# tactilePop.net
KiCad netlist of a schematic drawn in EAGLE
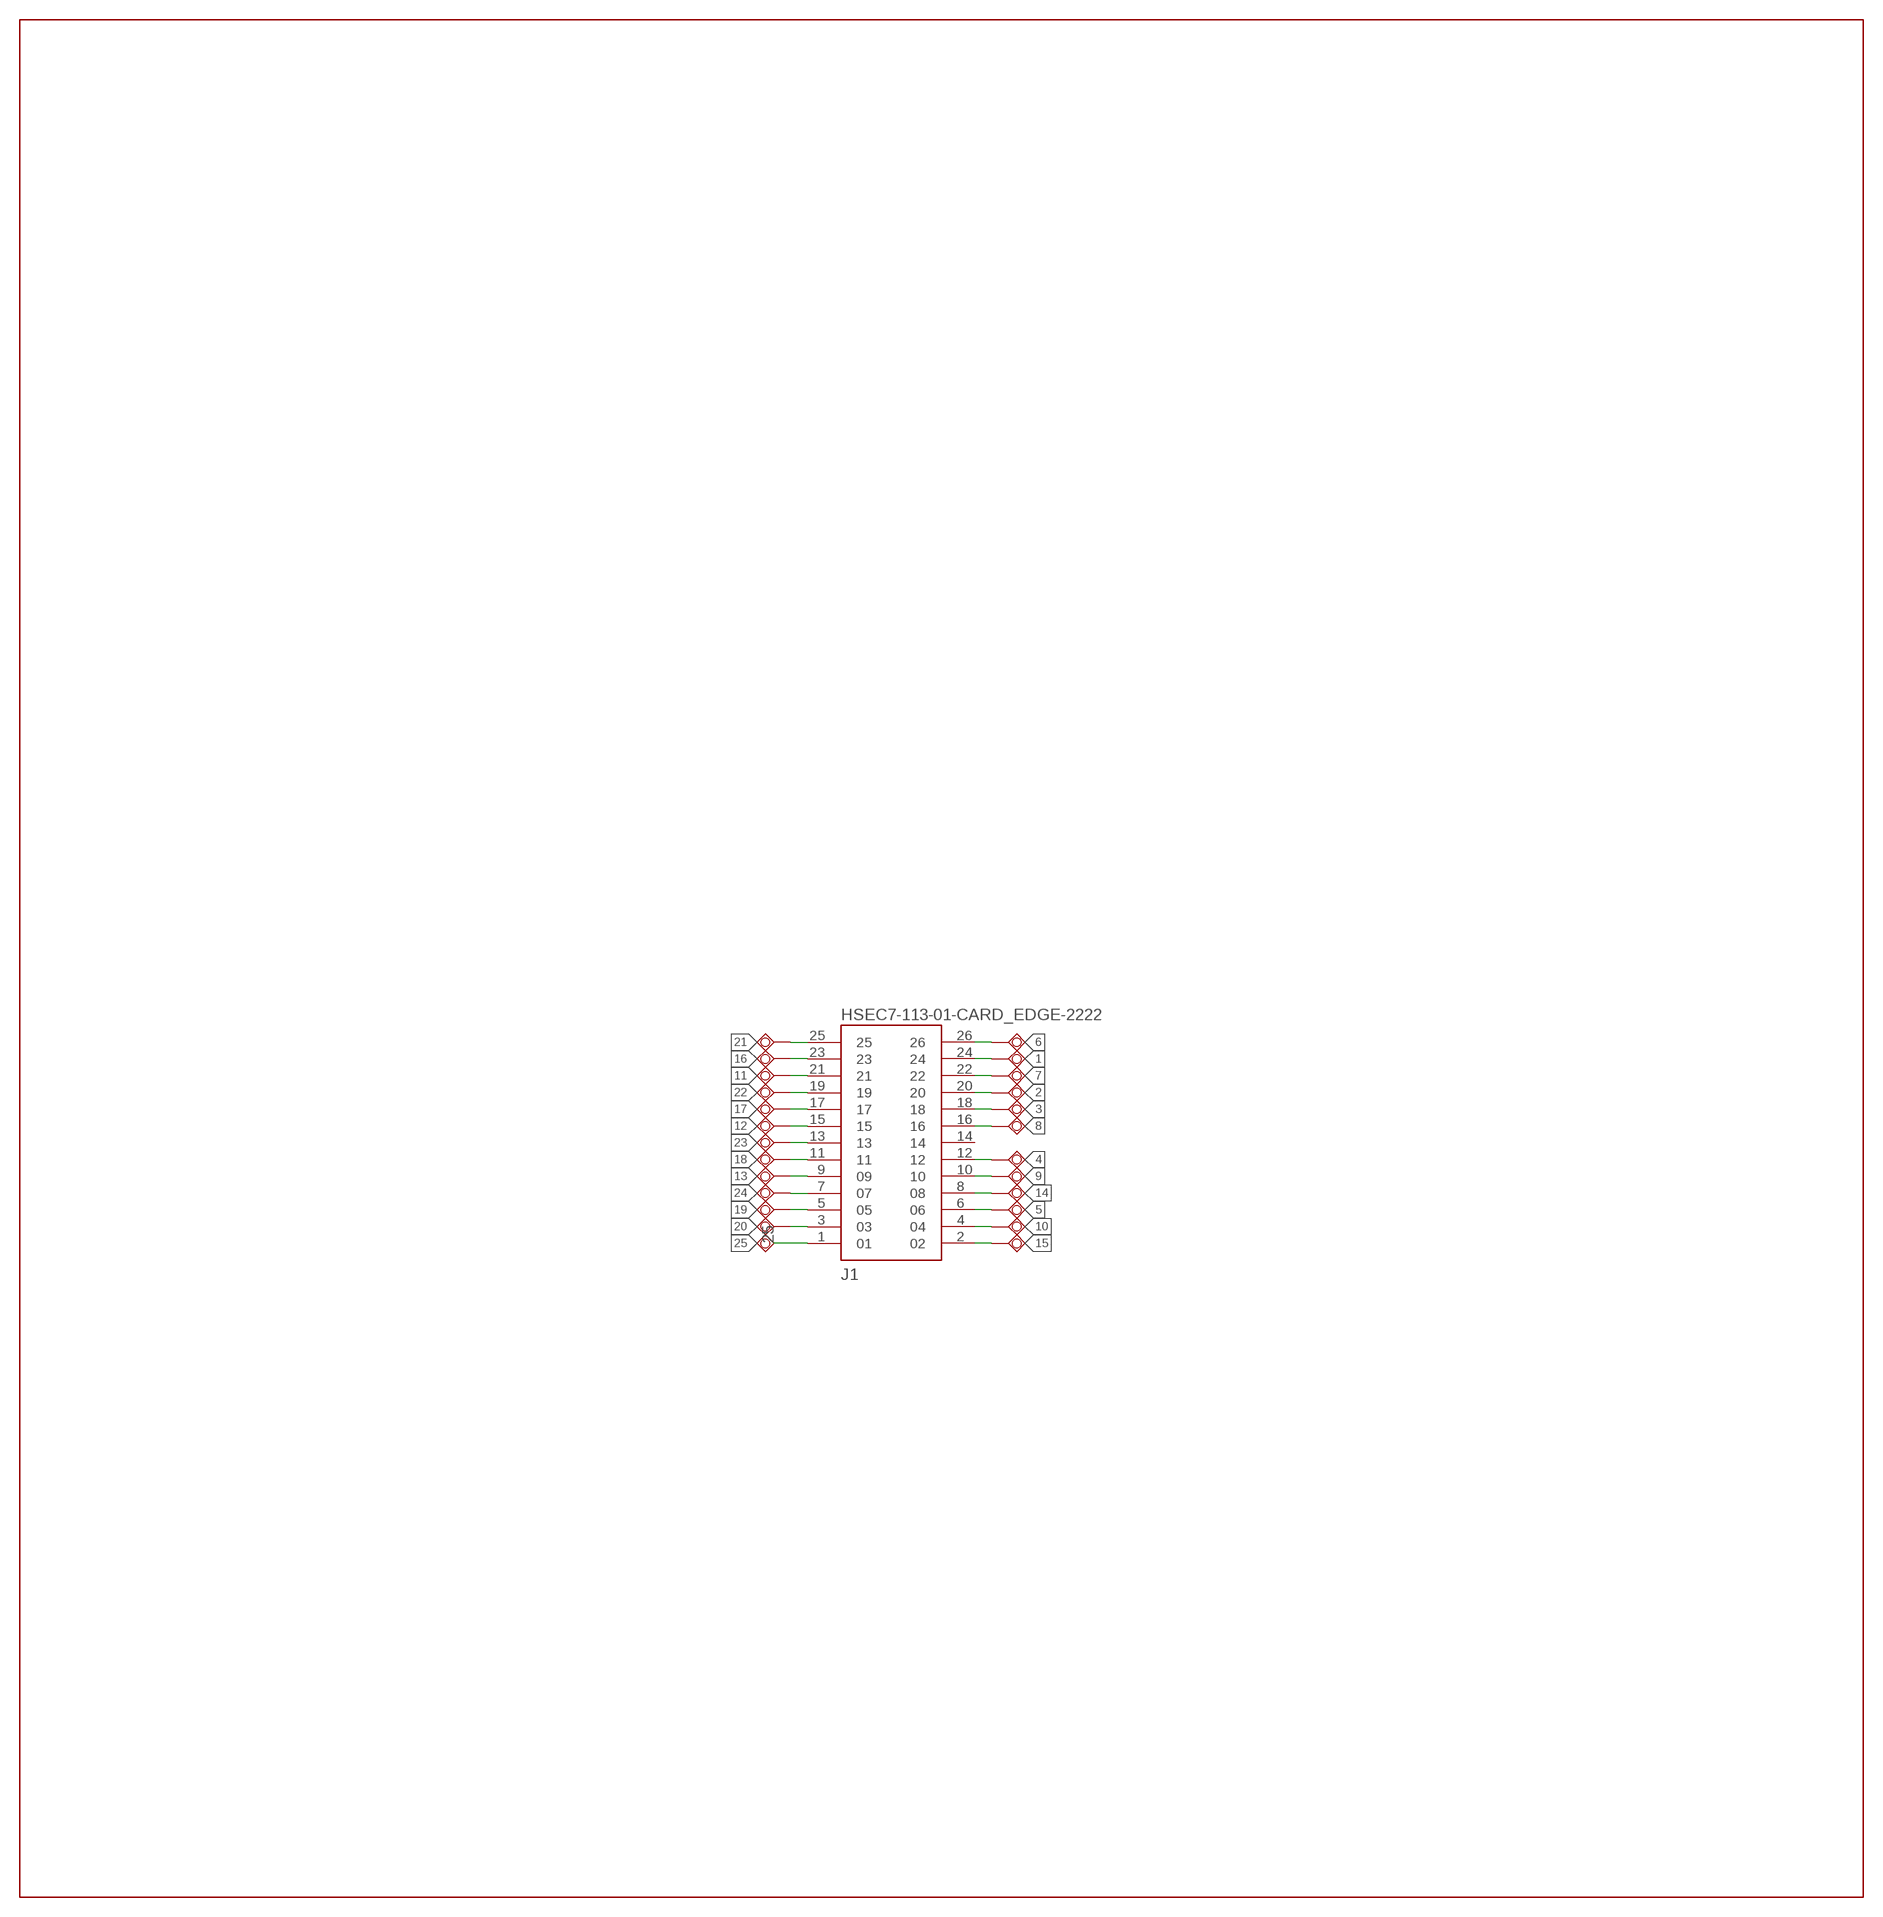
[diagram p0: schematic, sheet 1]

(export (version "E")
  (design (tool "Eeschema 10.0.6"))
  (components
    (comp (ref "1")
      (value "TESTPAD_TPSQB2,54")
      (footprint "eagle-import:TESTPAD_B2,54")
      (libsource (lib "eagle-import") (part "TESTPAD_TPSQB2,54"))
    )
    (comp (ref "2")
      (value "TESTPAD_TPSQB2,54")
      (footprint "eagle-import:TESTPAD_B2,54")
      (libsource (lib "eagle-import") (part "TESTPAD_TPSQB2,54"))
    )
    (comp (ref "3")
      (value "TESTPAD_TPSQB2,54")
      (footprint "eagle-import:TESTPAD_B2,54")
      (libsource (lib "eagle-import") (part "TESTPAD_TPSQB2,54"))
    )
    (comp (ref "J1")
      (value "HSEC7-113-01-CARD_EDGE-2222")
      (footprint "eagle-import:HSEC8-113-01-X-RA-L2")
      (libsource (lib "eagle-import") (part "HSEC7-113-01-CARD_EDGE-2222"))
    )
    (comp (ref "TP1")
      (value "TESTPAD_TPSQB2,54")
      (footprint "eagle-import:TESTPAD_B2,54")
      (libsource (lib "eagle-import") (part "TESTPAD_TPSQB2,54"))
    )
    (comp (ref "TP3")
      (value "TESTPAD_TPSQB2,54")
      (footprint "eagle-import:TESTPAD_B2,54")
      (libsource (lib "eagle-import") (part "TESTPAD_TPSQB2,54"))
    )
    (comp (ref "TP6")
      (value "TESTPAD_TPSQB2,54")
      (footprint "eagle-import:TESTPAD_B2,54")
      (libsource (lib "eagle-import") (part "TESTPAD_TPSQB2,54"))
    )
    (comp (ref "TP7")
      (value "TESTPAD_TPSQB2,54")
      (footprint "eagle-import:TESTPAD_B2,54")
      (libsource (lib "eagle-import") (part "TESTPAD_TPSQB2,54"))
    )
    (comp (ref "TP8")
      (value "TESTPAD_TPSQB2,54")
      (footprint "eagle-import:TESTPAD_B2,54")
      (libsource (lib "eagle-import") (part "TESTPAD_TPSQB2,54"))
    )
    (comp (ref "TP9")
      (value "TESTPAD_TPSQB2,54")
      (footprint "eagle-import:TESTPAD_B2,54")
      (libsource (lib "eagle-import") (part "TESTPAD_TPSQB2,54"))
    )
    (comp (ref "TP10")
      (value "TESTPAD_TPSQB2,54")
      (footprint "eagle-import:TESTPAD_B2,54")
      (libsource (lib "eagle-import") (part "TESTPAD_TPSQB2,54"))
    )
    (comp (ref "TP11")
      (value "TESTPAD_TPSQB2,54")
      (footprint "eagle-import:TESTPAD_B2,54")
      (libsource (lib "eagle-import") (part "TESTPAD_TPSQB2,54"))
    )
    (comp (ref "TP12")
      (value "TESTPAD_TPSQB2,54")
      (footprint "eagle-import:TESTPAD_B2,54")
      (libsource (lib "eagle-import") (part "TESTPAD_TPSQB2,54"))
    )
    (comp (ref "TP13")
      (value "TESTPAD_TPSQB2,54")
      (footprint "eagle-import:TESTPAD_B2,54")
      (libsource (lib "eagle-import") (part "TESTPAD_TPSQB2,54"))
    )
    (comp (ref "TP14")
      (value "TESTPAD_TPSQB2,54")
      (footprint "eagle-import:TESTPAD_B2,54")
      (libsource (lib "eagle-import") (part "TESTPAD_TPSQB2,54"))
    )
    (comp (ref "TP15")
      (value "TESTPAD_TPSQB2,54")
      (footprint "eagle-import:TESTPAD_B2,54")
      (libsource (lib "eagle-import") (part "TESTPAD_TPSQB2,54"))
    )
    (comp (ref "TP16")
      (value "TESTPAD_TPSQB2,54")
      (footprint "eagle-import:TESTPAD_B2,54")
      (libsource (lib "eagle-import") (part "TESTPAD_TPSQB2,54"))
    )
    (comp (ref "TP17")
      (value "TESTPAD_TPSQB2,54")
      (footprint "eagle-import:TESTPAD_B2,54")
      (libsource (lib "eagle-import") (part "TESTPAD_TPSQB2,54"))
    )
    (comp (ref "TP18")
      (value "TESTPAD_TPSQB2,54")
      (footprint "eagle-import:TESTPAD_B2,54")
      (libsource (lib "eagle-import") (part "TESTPAD_TPSQB2,54"))
    )
    (comp (ref "TP19")
      (value "TESTPAD_TPSQB2,54")
      (footprint "eagle-import:TESTPAD_B2,54")
      (libsource (lib "eagle-import") (part "TESTPAD_TPSQB2,54"))
    )
    (comp (ref "TP20")
      (value "TESTPAD_TPSQB2,54")
      (footprint "eagle-import:TESTPAD_B2,54")
      (libsource (lib "eagle-import") (part "TESTPAD_TPSQB2,54"))
    )
    (comp (ref "TP21")
      (value "TESTPAD_TPSQB2,54")
      (footprint "eagle-import:TESTPAD_B2,54")
      (libsource (lib "eagle-import") (part "TESTPAD_TPSQB2,54"))
    )
    (comp (ref "TP22")
      (value "TESTPAD_TPSQB2,54")
      (footprint "eagle-import:TESTPAD_B2,54")
      (libsource (lib "eagle-import") (part "TESTPAD_TPSQB2,54"))
    )
    (comp (ref "TP23")
      (value "TESTPAD_TPSQB2,54")
      (footprint "eagle-import:TESTPAD_B2,54")
      (libsource (lib "eagle-import") (part "TESTPAD_TPSQB2,54"))
    )
    (comp (ref "TP24")
      (value "TESTPAD_TPSQB2,54")
      (footprint "eagle-import:TESTPAD_B2,54")
      (libsource (lib "eagle-import") (part "TESTPAD_TPSQB2,54"))
    )
    (comp (ref "TP25")
      (value "TESTPAD_TPSQB2,54")
      (footprint "eagle-import:TESTPAD_B2,54")
      (libsource (lib "eagle-import") (part "TESTPAD_TPSQB2,54"))
    )
  )
  (nets
    (net (code "1") (name "1") (class "Default")
      (node (ref "1") (pin "TP") (pinfunction "TP_TP") (pintype "input"))
      (node (ref "J1") (pin "24") (pinfunction "24_24") (pintype "passive"))
    )
    (net (code "2") (name "2") (class "Default")
      (node (ref "2") (pin "TP") (pinfunction "TP_TP") (pintype "input"))
      (node (ref "J1") (pin "20") (pinfunction "20_20") (pintype "passive"))
    )
    (net (code "3") (name "3") (class "Default")
      (node (ref "3") (pin "TP") (pinfunction "TP_TP") (pintype "input"))
      (node (ref "J1") (pin "18") (pinfunction "18_18") (pintype "passive"))
    )
    (net (code "4") (name "4") (class "Default")
      (node (ref "J1") (pin "12") (pinfunction "12_12") (pintype "passive"))
      (node (ref "TP7") (pin "TP") (pinfunction "TP_TP") (pintype "input"))
    )
    (net (code "5") (name "5") (class "Default")
      (node (ref "J1") (pin "6") (pinfunction "06_6") (pintype "passive"))
      (node (ref "TP19") (pin "TP") (pinfunction "TP_TP") (pintype "input"))
    )
    (net (code "6") (name "6") (class "Default")
      (node (ref "J1") (pin "26") (pinfunction "26_26") (pintype "passive"))
      (node (ref "TP1") (pin "TP") (pinfunction "TP_TP") (pintype "input"))
    )
    (net (code "7") (name "7") (class "Default")
      (node (ref "J1") (pin "22") (pinfunction "22_22") (pintype "passive"))
      (node (ref "TP3") (pin "TP") (pinfunction "TP_TP") (pintype "input"))
    )
    (net (code "8") (name "8") (class "Default")
      (node (ref "J1") (pin "16") (pinfunction "16_16") (pintype "passive"))
      (node (ref "TP6") (pin "TP") (pinfunction "TP_TP") (pintype "input"))
    )
    (net (code "9") (name "9") (class "Default")
      (node (ref "J1") (pin "10") (pinfunction "10_10") (pintype "passive"))
      (node (ref "TP8") (pin "TP") (pinfunction "TP_TP") (pintype "input"))
    )
    (net (code "10") (name "10") (class "Default")
      (node (ref "J1") (pin "4") (pinfunction "04_4") (pintype "passive"))
      (node (ref "TP10") (pin "TP") (pinfunction "TP_TP") (pintype "input"))
    )
    (net (code "11") (name "11") (class "Default")
      (node (ref "J1") (pin "21") (pinfunction "21_21") (pintype "passive"))
      (node (ref "TP24") (pin "TP") (pinfunction "TP_TP") (pintype "input"))
    )
    (net (code "12") (name "12") (class "Default")
      (node (ref "J1") (pin "15") (pinfunction "15_15") (pintype "passive"))
      (node (ref "TP21") (pin "TP") (pinfunction "TP_TP") (pintype "input"))
    )
    (net (code "13") (name "13") (class "Default")
      (node (ref "J1") (pin "9") (pinfunction "09_9") (pintype "passive"))
      (node (ref "TP16") (pin "TP") (pinfunction "TP_TP") (pintype "input"))
    )
    (net (code "14") (name "14") (class "Default")
      (node (ref "J1") (pin "8") (pinfunction "08_8") (pintype "passive"))
      (node (ref "TP20") (pin "TP") (pinfunction "TP_TP") (pintype "input"))
    )
    (net (code "15") (name "15") (class "Default")
      (node (ref "J1") (pin "2") (pinfunction "02_2") (pintype "passive"))
      (node (ref "TP11") (pin "TP") (pinfunction "TP_TP") (pintype "input"))
    )
    (net (code "16") (name "16") (class "Default")
      (node (ref "J1") (pin "23") (pinfunction "23_23") (pintype "passive"))
      (node (ref "TP25") (pin "TP") (pinfunction "TP_TP") (pintype "input"))
    )
    (net (code "17") (name "17") (class "Default")
      (node (ref "J1") (pin "17") (pinfunction "17_17") (pintype "passive"))
      (node (ref "TP22") (pin "TP") (pinfunction "TP_TP") (pintype "input"))
    )
    (net (code "18") (name "18") (class "Default")
      (node (ref "J1") (pin "11") (pinfunction "11_11") (pintype "passive"))
      (node (ref "TP17") (pin "TP") (pinfunction "TP_TP") (pintype "input"))
    )
    (net (code "19") (name "19") (class "Default")
      (node (ref "J1") (pin "5") (pinfunction "05_5") (pintype "passive"))
      (node (ref "TP14") (pin "TP") (pinfunction "TP_TP") (pintype "input"))
    )
    (net (code "20") (name "20") (class "Default")
      (node (ref "J1") (pin "3") (pinfunction "03_3") (pintype "passive"))
      (node (ref "TP13") (pin "TP") (pinfunction "TP_TP") (pintype "input"))
    )
    (net (code "21") (name "21") (class "Default")
      (node (ref "J1") (pin "25") (pinfunction "25_25") (pintype "passive"))
      (node (ref "TP9") (pin "TP") (pinfunction "TP_TP") (pintype "input"))
    )
    (net (code "22") (name "22") (class "Default")
      (node (ref "J1") (pin "19") (pinfunction "19_19") (pintype "passive"))
      (node (ref "TP23") (pin "TP") (pinfunction "TP_TP") (pintype "input"))
    )
    (net (code "23") (name "23") (class "Default")
      (node (ref "J1") (pin "13") (pinfunction "13_13") (pintype "passive"))
      (node (ref "TP18") (pin "TP") (pinfunction "TP_TP") (pintype "input"))
    )
    (net (code "24") (name "24") (class "Default")
      (node (ref "J1") (pin "7") (pinfunction "07_7") (pintype "passive"))
      (node (ref "TP15") (pin "TP") (pinfunction "TP_TP") (pintype "input"))
    )
    (net (code "25") (name "25") (class "Default")
      (node (ref "J1") (pin "1") (pinfunction "01_1") (pintype "passive"))
      (node (ref "TP12") (pin "TP") (pinfunction "TP_TP") (pintype "input"))
    )
    (net (code "26") (name "unconnected-(J1-Pad14)") (class "Default")
      (node (ref "J1") (pin "14") (pinfunction "14_14") (pintype "passive"))
    )
  )
)
